# MSP-EXP430F5529LP_1.net
KiCad netlist of a schematic drawn in Altium Designer
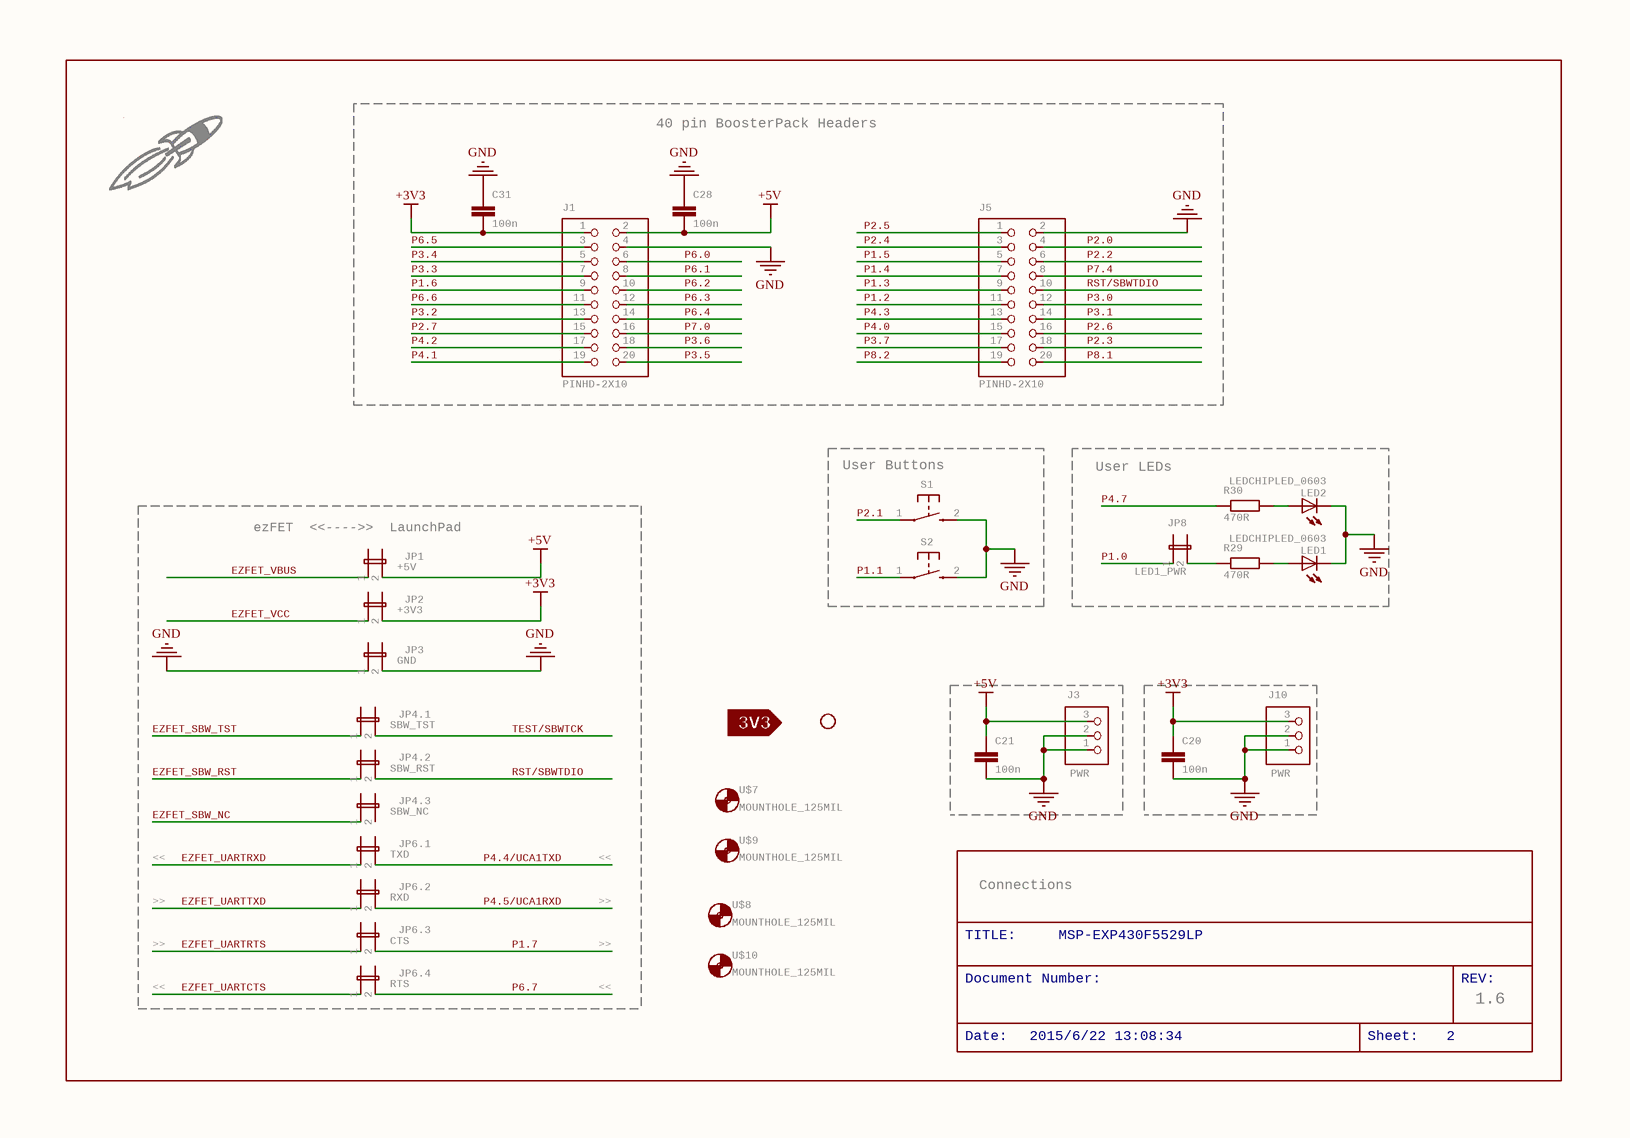
[diagram p0: MSP-EXP430F5529LP_1.SchDoc]

(export (version "E")
  (design (tool "Eeschema 10.0.6"))
  (components
    (comp (ref "C20")
      (value "100n")
      (footprint "0402")
      (description "CAPACITOR, European symbol")
      (libsource (lib "rcl") (part "C-EUCM0402"))
    )
    (comp (ref "C21")
      (value "100n")
      (footprint "0402")
      (description "CAPACITOR, European symbol")
      (libsource (lib "rcl") (part "C-EUCM0402"))
    )
    (comp (ref "C28")
      (value "100n")
      (footprint "0402")
      (description "CAPACITOR, European symbol")
      (libsource (lib "rcl") (part "C-EUCM0402"))
    )
    (comp (ref "C31")
      (value "100n")
      (footprint "0402")
      (description "CAPACITOR, European symbol")
      (libsource (lib "rcl") (part "C-EUCM0402"))
    )
    (comp (ref "DRAW1")
      (value "LOGO-ROCKET-20X13MM-SCH-S")
      (footprint "LOGO-ROCKET-10X7MM-BRD")
      (libsource (lib "TI-LaunchPad-Eagle") (part "LOGO-ROCKET-20X13MM-SCH-S"))
    )
    (comp (ref "J1")
      (value "PINHD-2X10")
      (footprint "2X10")
      (description "PIN HEADER")
      (fields (field (name "LIBRARYNAME") "pinhead"))
      (libsource (lib "pinhead") (part "PINHD-2X10"))
    )
    (comp (ref "J3")
      (value "PWR")
      (footprint "1X03")
      (description "PIN HEADER")
      (fields (field (name "LIBRARYNAME") "pinhead"))
      (libsource (lib "pinhead") (part "PINHD-1X3"))
    )
    (comp (ref "J5")
      (value "PINHD-2X10")
      (footprint "2X10")
      (description "PIN HEADER")
      (fields (field (name "LIBRARYNAME") "pinhead"))
      (libsource (lib "pinhead") (part "PINHD-2X10"))
    )
    (comp (ref "J10")
      (value "PWR")
      (footprint "1X03")
      (description "PIN HEADER")
      (fields (field (name "LIBRARYNAME") "pinhead"))
      (libsource (lib "pinhead") (part "PINHD-1X3"))
    )
    (comp (ref "JP1") (value "+5V") (footprint "JP1M") (libsource (lib "jumper") (part "JP1M")))
    (comp (ref "JP2") (value "+3V3") (footprint "JP1M") (libsource (lib "jumper") (part "JP1M")))
    (comp (ref "JP3") (value "GND") (footprint "JP1M") (libsource (lib "jumper") (part "JP1M")))
    (comp (ref "JP4.1") (value "SBW_TST") (footprint "JP1M") (libsource (lib "jumper") (part "JP1M")))
    (comp (ref "JP4.2") (value "SBW_RST") (footprint "JP1M") (libsource (lib "jumper") (part "JP1M")))
    (comp (ref "JP4.3") (value "SBW_NC") (footprint "JP1M") (libsource (lib "jumper") (part "JP1M")))
    (comp (ref "JP6.1") (value "TXD") (footprint "JP1M") (libsource (lib "jumper") (part "JP1M")))
    (comp (ref "JP6.2") (value "RXD") (footprint "JP1M") (libsource (lib "jumper") (part "JP1M")))
    (comp (ref "JP6.3") (value "CTS") (footprint "JP1M") (libsource (lib "jumper") (part "JP1M")))
    (comp (ref "JP6.4") (value "RTS") (footprint "JP1M") (libsource (lib "jumper") (part "JP1M")))
    (comp (ref "JP8")
      (value "LED1_PWR")
      (footprint "JP1")
      (description "JUMPER")
      (libsource (lib "jumper") (part "JP1E"))
    )
    (comp (ref "LED1")
      (value "LEDCHIPLED_0603")
      (footprint "CHIPLED_0603")
      (libsource (lib "led") (part "LEDCHIPLED_0603"))
    )
    (comp (ref "LED2")
      (value "LEDCHIPLED_0603")
      (footprint "CHIPLED_0603")
      (libsource (lib "led") (part "LEDCHIPLED_0603"))
    )
    (comp (ref "R29")
      (value "470R")
      (footprint "0402")
      (description "RESISTOR, European symbol")
      (libsource (lib "rcl") (part "R-EU_RM0402"))
    )
    (comp (ref "R30")
      (value "470R")
      (footprint "0402")
      (description "RESISTOR, European symbol")
      (libsource (lib "rcl") (part "R-EU_RM0402"))
    )
    (comp (ref "S1")
      (value "PB")
      (footprint "PBTH")
      (description "OMRON SWITCH")
      (fields (field (name "LIBRARYNAME") "electricalmeter"))
      (libsource (lib "electricalmeter") (part "PB"))
    )
    (comp (ref "S2")
      (value "PB")
      (footprint "PBTH")
      (description "OMRON SWITCH")
      (fields (field (name "LIBRARYNAME") "electricalmeter"))
      (libsource (lib "electricalmeter") (part "PB"))
    )
    (comp (ref "U$4") (value "MS_TM") (footprint "MS_TM") (libsource (lib "LP_Silkscreen") (part "MS_TM")))
    (comp (ref "U$6")
      (value "SILK_3V3_TAG")
      (footprint "SILK_3V3_TAG")
      (libsource (lib "MSP-EXP432") (part "SILK_3V3_TAG"))
    )
    (comp (ref "U$7")
      (value "MOUNTHOLE_125MIL")
      (footprint "MOUNTHOLE_125MIL")
      (libsource (lib "MSP-EXP432") (part "MOUNTHOLE_125MIL"))
    )
    (comp (ref "U$8")
      (value "MOUNTHOLE_125MIL")
      (footprint "MOUNTHOLE_125MIL")
      (libsource (lib "MSP-EXP432") (part "MOUNTHOLE_125MIL"))
    )
    (comp (ref "U$9")
      (value "MOUNTHOLE_125MIL")
      (footprint "MOUNTHOLE_125MIL")
      (libsource (lib "MSP-EXP432") (part "MOUNTHOLE_125MIL"))
    )
    (comp (ref "U$10")
      (value "MOUNTHOLE_125MIL")
      (footprint "MOUNTHOLE_125MIL")
      (libsource (lib "MSP-EXP432") (part "MOUNTHOLE_125MIL"))
    )
    (comp (ref "U$11")
      (value "5529LP_REARSILK_REV1_6")
      (footprint "5529LP_REARSILK_REV1_6")
      (libsource (lib "Silk") (part "5529LP_REARSILK_REV1_6"))
    )
  )
  (nets
    (net (code "1") (name "+3V3") (class "Default")
      (node (ref "C20") (pin "1") (pinfunction "1_1") (pintype "passive"))
      (node (ref "C31") (pin "2") (pinfunction "2_2") (pintype "passive"))
      (node (ref "J1") (pin "1") (pinfunction "1_1") (pintype "passive"))
      (node (ref "J10") (pin "3") (pinfunction "3_3") (pintype "passive"))
      (node (ref "JP2") (pin "2") (pinfunction "2_2") (pintype "passive"))
    )
    (net (code "2") (name "+5V") (class "Default")
      (node (ref "C21") (pin "1") (pinfunction "1_1") (pintype "passive"))
      (node (ref "C28") (pin "2") (pinfunction "2_2") (pintype "passive"))
      (node (ref "J1") (pin "2") (pinfunction "2_2") (pintype "passive"))
      (node (ref "J3") (pin "3") (pinfunction "3_3") (pintype "passive"))
      (node (ref "JP1") (pin "2") (pinfunction "2_2") (pintype "passive"))
    )
    (net (code "3") (name "/EZFET_SBW_NC") (class "Default")
      (node (ref "JP4.3") (pin "1") (pinfunction "1_1") (pintype "passive"))
    )
    (net (code "4") (name "/EZFET_SBW_RST") (class "Default")
      (node (ref "JP4.2") (pin "1") (pinfunction "1_1") (pintype "passive"))
    )
    (net (code "5") (name "/EZFET_SBW_TST") (class "Default")
      (node (ref "JP4.1") (pin "1") (pinfunction "1_1") (pintype "passive"))
    )
    (net (code "6") (name "/EZFET_UARTCTS") (class "Default")
      (node (ref "JP6.4") (pin "1") (pinfunction "1_1") (pintype "passive"))
    )
    (net (code "7") (name "/EZFET_UARTRTS") (class "Default")
      (node (ref "JP6.3") (pin "1") (pinfunction "1_1") (pintype "passive"))
    )
    (net (code "8") (name "/EZFET_UARTRXD") (class "Default")
      (node (ref "JP6.1") (pin "1") (pinfunction "1_1") (pintype "passive"))
    )
    (net (code "9") (name "/EZFET_UARTTXD") (class "Default")
      (node (ref "JP6.2") (pin "1") (pinfunction "1_1") (pintype "passive"))
    )
    (net (code "10") (name "/EZFET_VBUS") (class "Default")
      (node (ref "JP1") (pin "1") (pinfunction "1_1") (pintype "passive"))
    )
    (net (code "11") (name "/EZFET_VCC") (class "Default")
      (node (ref "JP2") (pin "1") (pinfunction "1_1") (pintype "passive"))
    )
    (net (code "12") (name "/P1.0") (class "Default")
      (node (ref "JP8") (pin "1") (pinfunction "1_1") (pintype "passive"))
    )
    (net (code "13") (name "/P1.1") (class "Default")
      (node (ref "S2") (pin "1") (pinfunction "P_1") (pintype "passive"))
    )
    (net (code "14") (name "/P1.2") (class "Default")
      (node (ref "J5") (pin "11") (pinfunction "11_11") (pintype "passive"))
    )
    (net (code "15") (name "/P1.3") (class "Default")
      (node (ref "J5") (pin "9") (pinfunction "9_9") (pintype "passive"))
    )
    (net (code "16") (name "/P1.4") (class "Default")
      (node (ref "J5") (pin "7") (pinfunction "7_7") (pintype "passive"))
    )
    (net (code "17") (name "/P1.5") (class "Default")
      (node (ref "J5") (pin "5") (pinfunction "5_5") (pintype "passive"))
    )
    (net (code "18") (name "/P1.6") (class "Default")
      (node (ref "J1") (pin "9") (pinfunction "9_9") (pintype "passive"))
    )
    (net (code "19") (name "/P1.7") (class "Default")
      (node (ref "JP6.3") (pin "2") (pinfunction "2_2") (pintype "passive"))
    )
    (net (code "20") (name "/P2.0") (class "Default")
      (node (ref "J5") (pin "4") (pinfunction "4_4") (pintype "passive"))
    )
    (net (code "21") (name "/P2.1") (class "Default")
      (node (ref "S1") (pin "1") (pinfunction "P_1") (pintype "passive"))
    )
    (net (code "22") (name "/P2.2") (class "Default")
      (node (ref "J5") (pin "6") (pinfunction "6_6") (pintype "passive"))
    )
    (net (code "23") (name "/P2.3") (class "Default")
      (node (ref "J5") (pin "18") (pinfunction "18_18") (pintype "passive"))
    )
    (net (code "24") (name "/P2.4") (class "Default")
      (node (ref "J5") (pin "3") (pinfunction "3_3") (pintype "passive"))
    )
    (net (code "25") (name "/P2.5") (class "Default")
      (node (ref "J5") (pin "1") (pinfunction "1_1") (pintype "passive"))
    )
    (net (code "26") (name "/P2.6") (class "Default")
      (node (ref "J5") (pin "16") (pinfunction "16_16") (pintype "passive"))
    )
    (net (code "27") (name "/P2.7") (class "Default")
      (node (ref "J1") (pin "15") (pinfunction "15_15") (pintype "passive"))
    )
    (net (code "28") (name "/P3.0") (class "Default")
      (node (ref "J5") (pin "12") (pinfunction "12_12") (pintype "passive"))
    )
    (net (code "29") (name "/P3.1") (class "Default")
      (node (ref "J5") (pin "14") (pinfunction "14_14") (pintype "passive"))
    )
    (net (code "30") (name "/P3.2") (class "Default")
      (node (ref "J1") (pin "13") (pinfunction "13_13") (pintype "passive"))
    )
    (net (code "31") (name "/P3.3") (class "Default")
      (node (ref "J1") (pin "7") (pinfunction "7_7") (pintype "passive"))
    )
    (net (code "32") (name "/P3.4") (class "Default")
      (node (ref "J1") (pin "5") (pinfunction "5_5") (pintype "passive"))
    )
    (net (code "33") (name "/P3.5") (class "Default")
      (node (ref "J1") (pin "20") (pinfunction "20_20") (pintype "passive"))
    )
    (net (code "34") (name "/P3.6") (class "Default")
      (node (ref "J1") (pin "18") (pinfunction "18_18") (pintype "passive"))
    )
    (net (code "35") (name "/P3.7") (class "Default")
      (node (ref "J5") (pin "17") (pinfunction "17_17") (pintype "passive"))
    )
    (net (code "36") (name "/P4.0") (class "Default")
      (node (ref "J5") (pin "15") (pinfunction "15_15") (pintype "passive"))
    )
    (net (code "37") (name "/P4.1") (class "Default")
      (node (ref "J1") (pin "19") (pinfunction "19_19") (pintype "passive"))
    )
    (net (code "38") (name "/P4.2") (class "Default")
      (node (ref "J1") (pin "17") (pinfunction "17_17") (pintype "passive"))
    )
    (net (code "39") (name "/P4.3") (class "Default")
      (node (ref "J5") (pin "13") (pinfunction "13_13") (pintype "passive"))
    )
    (net (code "40") (name "/P4.4{slash}UCA1TXD") (class "Default")
      (node (ref "JP6.1") (pin "2") (pinfunction "2_2") (pintype "passive"))
    )
    (net (code "41") (name "/P4.5{slash}UCA1RXD") (class "Default")
      (node (ref "JP6.2") (pin "2") (pinfunction "2_2") (pintype "passive"))
    )
    (net (code "42") (name "/P4.7") (class "Default")
      (node (ref "R30") (pin "1") (pinfunction "1_1") (pintype "passive"))
    )
    (net (code "43") (name "/P6.0") (class "Default")
      (node (ref "J1") (pin "6") (pinfunction "6_6") (pintype "passive"))
    )
    (net (code "44") (name "/P6.1") (class "Default")
      (node (ref "J1") (pin "8") (pinfunction "8_8") (pintype "passive"))
    )
    (net (code "45") (name "/P6.2") (class "Default")
      (node (ref "J1") (pin "10") (pinfunction "10_10") (pintype "passive"))
    )
    (net (code "46") (name "/P6.3") (class "Default")
      (node (ref "J1") (pin "12") (pinfunction "12_12") (pintype "passive"))
    )
    (net (code "47") (name "/P6.4") (class "Default")
      (node (ref "J1") (pin "14") (pinfunction "14_14") (pintype "passive"))
    )
    (net (code "48") (name "/P6.5") (class "Default")
      (node (ref "J1") (pin "3") (pinfunction "3_3") (pintype "passive"))
    )
    (net (code "49") (name "/P6.6") (class "Default")
      (node (ref "J1") (pin "11") (pinfunction "11_11") (pintype "passive"))
    )
    (net (code "50") (name "/P6.7") (class "Default")
      (node (ref "JP6.4") (pin "2") (pinfunction "2_2") (pintype "passive"))
    )
    (net (code "51") (name "/P7.0") (class "Default")
      (node (ref "J1") (pin "16") (pinfunction "16_16") (pintype "passive"))
    )
    (net (code "52") (name "/P7.4") (class "Default")
      (node (ref "J5") (pin "8") (pinfunction "8_8") (pintype "passive"))
    )
    (net (code "53") (name "/P8.1") (class "Default")
      (node (ref "J5") (pin "20") (pinfunction "20_20") (pintype "passive"))
    )
    (net (code "54") (name "/P8.2") (class "Default")
      (node (ref "J5") (pin "19") (pinfunction "19_19") (pintype "passive"))
    )
    (net (code "55") (name "/RST{slash}SBWTDIO") (class "Default")
      (node (ref "J5") (pin "10") (pinfunction "10_10") (pintype "passive"))
      (node (ref "JP4.2") (pin "2") (pinfunction "2_2") (pintype "passive"))
    )
    (net (code "56") (name "/TEST{slash}SBWTCK") (class "Default")
      (node (ref "JP4.1") (pin "2") (pinfunction "2_2") (pintype "passive"))
    )
    (net (code "57") (name "GND") (class "Default")
      (node (ref "C20") (pin "2") (pinfunction "2_2") (pintype "passive"))
      (node (ref "C21") (pin "2") (pinfunction "2_2") (pintype "passive"))
      (node (ref "C28") (pin "1") (pinfunction "1_1") (pintype "passive"))
      (node (ref "C31") (pin "1") (pinfunction "1_1") (pintype "passive"))
      (node (ref "J1") (pin "4") (pinfunction "4_4") (pintype "passive"))
      (node (ref "J10") (pin "1") (pinfunction "1_1") (pintype "passive"))
      (node (ref "J10") (pin "2") (pinfunction "2_2") (pintype "passive"))
      (node (ref "J3") (pin "1") (pinfunction "1_1") (pintype "passive"))
      (node (ref "J3") (pin "2") (pinfunction "2_2") (pintype "passive"))
      (node (ref "J5") (pin "2") (pinfunction "2_2") (pintype "passive"))
      (node (ref "JP3") (pin "1") (pinfunction "1_1") (pintype "passive"))
      (node (ref "JP3") (pin "2") (pinfunction "2_2") (pintype "passive"))
      (node (ref "LED1") (pin "C") (pinfunction "C_C") (pintype "passive"))
      (node (ref "LED2") (pin "C") (pinfunction "C_C") (pintype "passive"))
      (node (ref "S1") (pin "2") (pinfunction "S_2") (pintype "passive"))
      (node (ref "S2") (pin "2") (pinfunction "S_2") (pintype "passive"))
    )
    (net (code "58") (name "Net-(JP8-Pad2)") (class "Default")
      (node (ref "JP8") (pin "2") (pinfunction "2_2") (pintype "passive"))
      (node (ref "R29") (pin "1") (pinfunction "1_1") (pintype "passive"))
    )
    (net (code "59") (name "Net-(LED1-PadA)") (class "Default")
      (node (ref "LED1") (pin "A") (pinfunction "A_A") (pintype "passive"))
      (node (ref "R29") (pin "2") (pinfunction "2_2") (pintype "passive"))
    )
    (net (code "60") (name "Net-(LED2-PadA)") (class "Default")
      (node (ref "LED2") (pin "A") (pinfunction "A_A") (pintype "passive"))
      (node (ref "R30") (pin "2") (pinfunction "2_2") (pintype "passive"))
    )
    (net (code "61") (name "unconnected-(JP4.3-Pad2)") (class "Default")
      (node (ref "JP4.3") (pin "2") (pinfunction "2_2") (pintype "passive"))
    )
  )
)
